# W-F-DX-C1_Display_PCB.net
KiCad netlist of a schematic drawn in Altium Designer
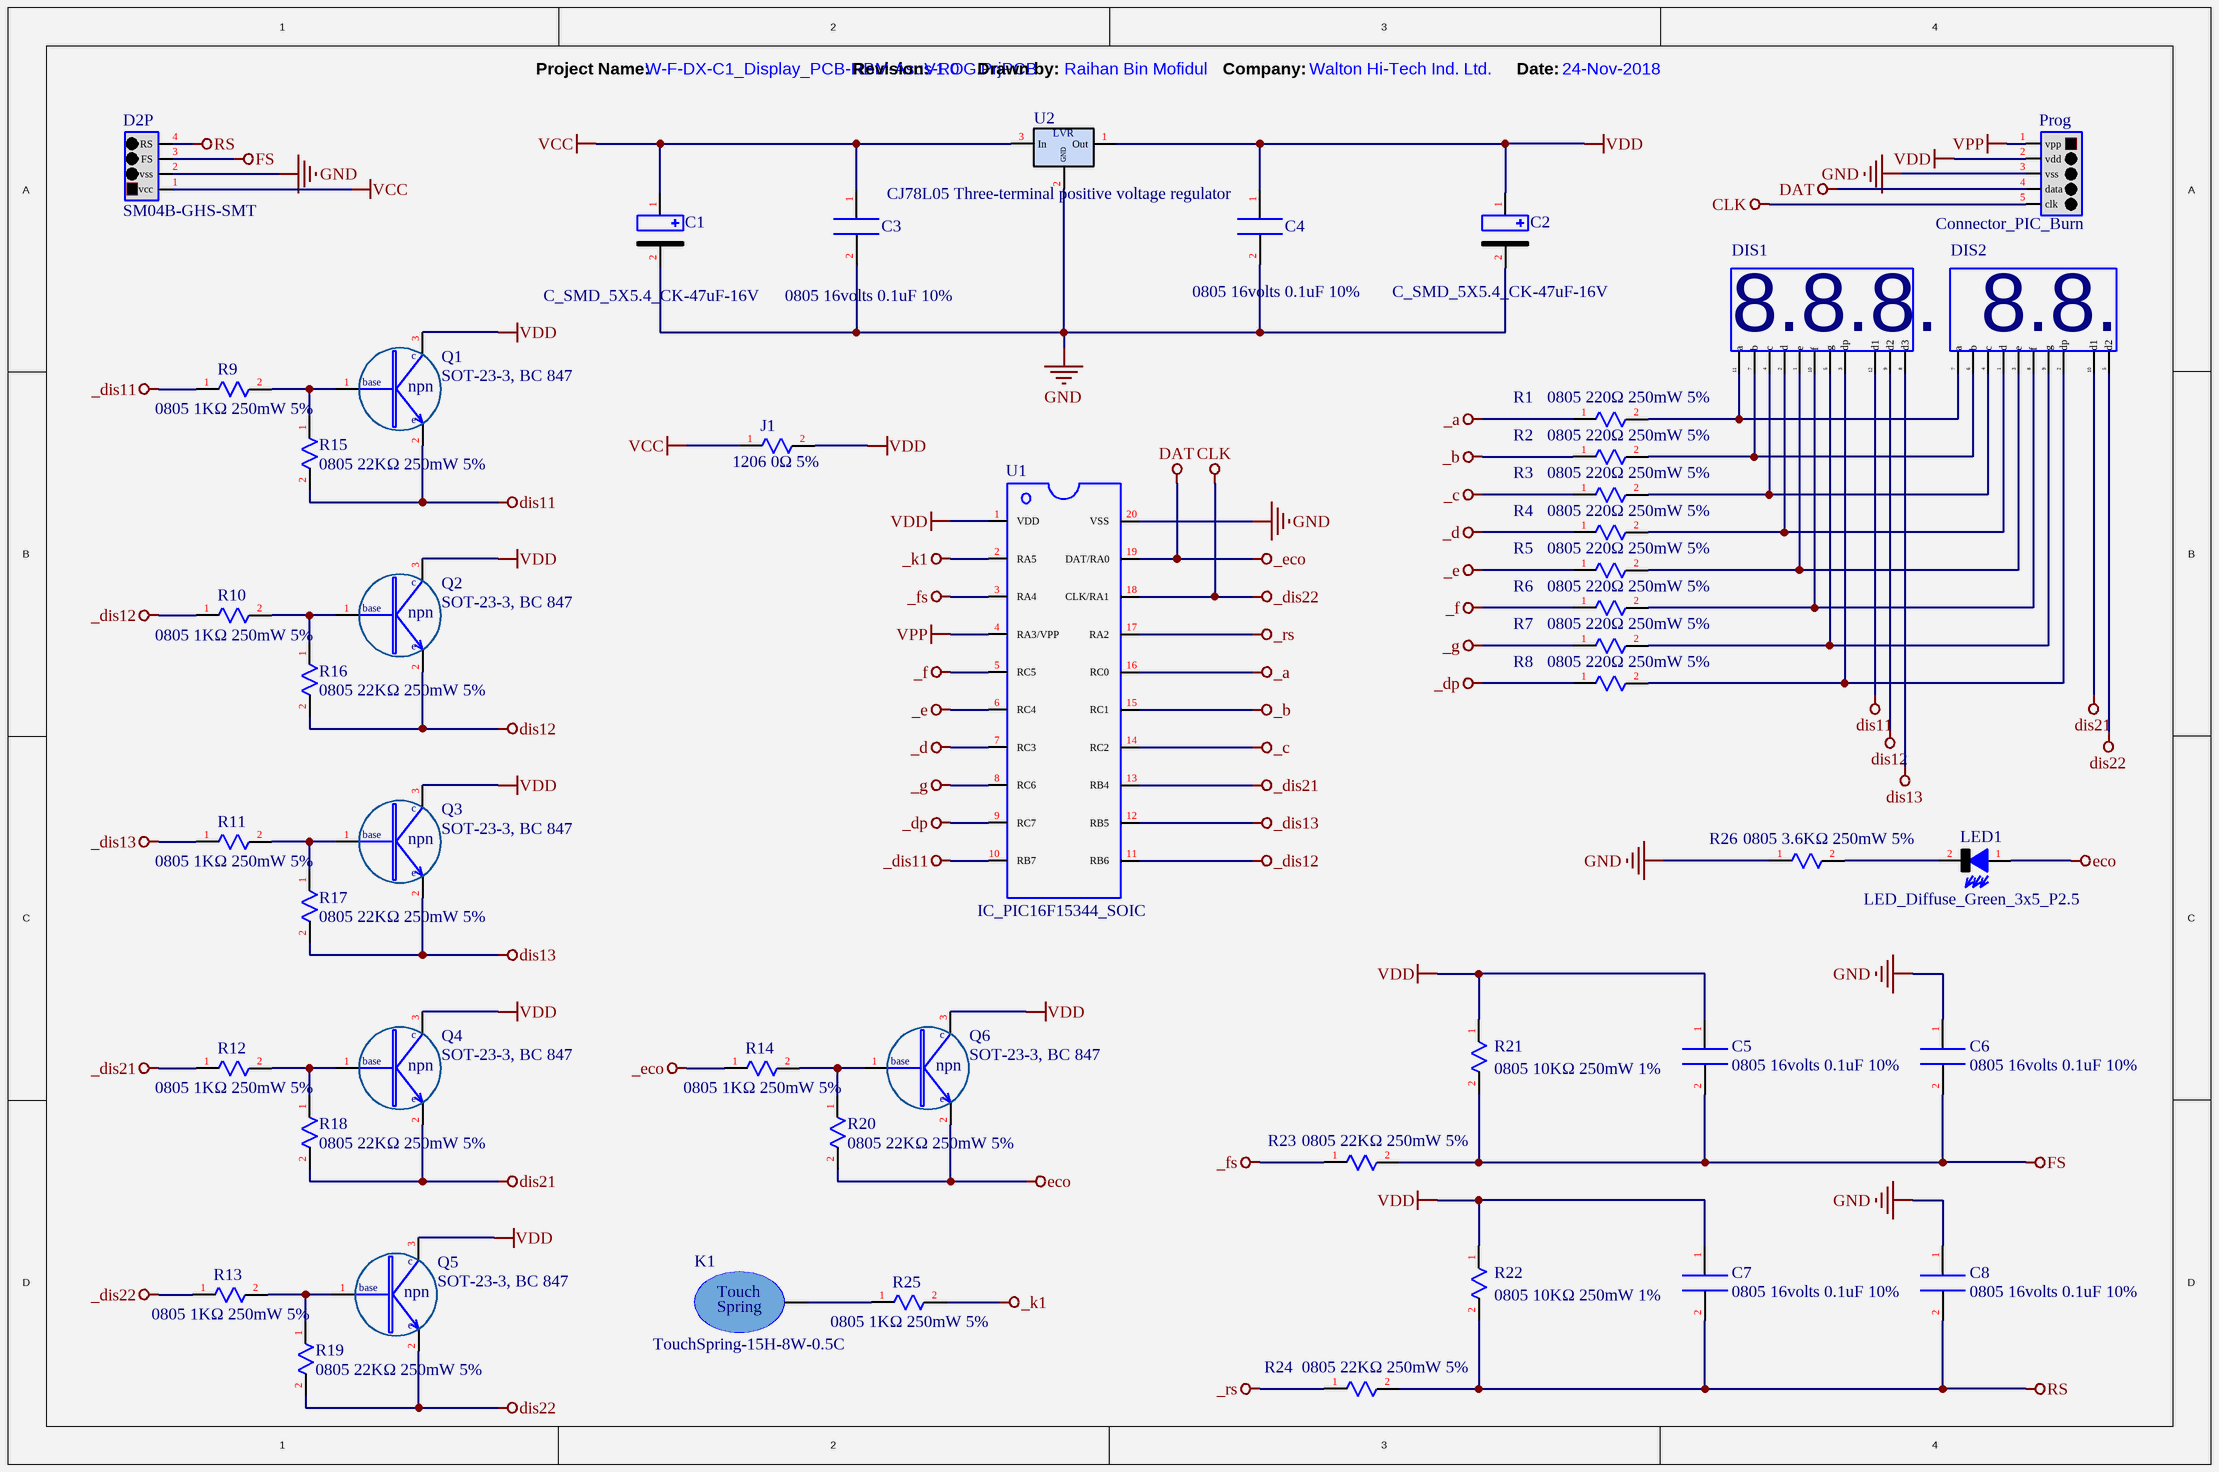
[diagram p0: W-F-DX-C1_Display_PCB.SchDoc]

(export (version "E")
  (design (tool "Eeschema 10.0.6"))
  (components
    (comp (ref "C1")
      (value "C_SMD_5X5.4_CK-47uF-16V")
      (footprint "C_SMD_5X5.4_CK-47uF-16V")
      (libsource (lib "RBM_SCH-Lib_17-Nov-18") (part "Capacitor Polar"))
    )
    (comp (ref "C2")
      (value "C_SMD_5X5.4_CK-47uF-16V")
      (footprint "C_SMD_5X5.4_CK-47uF-16V")
      (libsource (lib "RBM_SCH-Lib_17-Nov-18") (part "Capacitor Polar"))
    )
    (comp (ref "C3")
      (value "0805 16volts 0.1uF 10%")
      (footprint "C_0805")
      (libsource (lib "RBM_SCH-Lib_17-Nov-18") (part "Capacitor Non-Polar"))
    )
    (comp (ref "C4")
      (value "0805 16volts 0.1uF 10%")
      (footprint "C_0805")
      (libsource (lib "RBM_SCH-Lib_17-Nov-18") (part "Capacitor Non-Polar"))
    )
    (comp (ref "C5")
      (value "0805 16volts 0.1uF 10%")
      (footprint "C_0805")
      (libsource (lib "RBM_SCH-Lib_17-Nov-18") (part "Capacitor Non-Polar"))
    )
    (comp (ref "C6")
      (value "0805 16volts 0.1uF 10%")
      (footprint "C_0805")
      (libsource (lib "RBM_SCH-Lib_17-Nov-18") (part "Capacitor Non-Polar"))
    )
    (comp (ref "C7")
      (value "0805 16volts 0.1uF 10%")
      (footprint "C_0805")
      (libsource (lib "RBM_SCH-Lib_17-Nov-18") (part "Capacitor Non-Polar"))
    )
    (comp (ref "C8")
      (value "0805 16volts 0.1uF 10%")
      (footprint "C_0805")
      (libsource (lib "RBM_SCH-Lib_17-Nov-18") (part "Capacitor Non-Polar"))
    )
    (comp (ref "D2P")
      (value "SM04B-GHS-SMT")
      (footprint "CN_4P_A2001WR-S-XP-LCP")
      (libsource (lib "RBM_V1.0_Schlib") (part "Connector_4PINs"))
    )
    (comp (ref "DIS1")
      (value "Display_3Digits Seven Segment")
      (footprint "DIS_56\" 3 digit Display")
      (description "3 Digit Seven Segment Display CA")
      (libsource (lib "RBM_SCH-Lib_17-Nov-18") (part "Display_3Digits Seven Segment"))
    )
    (comp (ref "DIS2")
      (value "Display_2Digits Seven Segment")
      (footprint "Dis_56\" 2 digit Display")
      (description "2 Digit Seven Segment Display CA")
      (libsource (lib "RBM_SCH-Lib_17-Nov-18") (part "Display_2Digits Seven Segment"))
    )
    (comp (ref "J1")
      (value "1206 0Ω 5%")
      (footprint "R_1206")
      (libsource (lib "RBM_SCH-Lib_17-Nov-18") (part "Resistor"))
    )
    (comp (ref "K1")
      (value "TouchSpring-15H-8W-0.5C")
      (footprint "T_TouchSpring-15H-8W-0.5C")
      (libsource (lib "RBM_SCH-Lib_17-Nov-18") (part "Touch_Spring"))
    )
    (comp (ref "LED1")
      (value "LED_Diffuse_Green_3x5_P2.5")
      (footprint "LED_3x5_P2.5")
      (libsource (lib "RBM_SCH-Lib_17-Nov-18") (part "LED"))
    )
    (comp (ref "Prog")
      (value "Connector_PIC_Burn")
      (footprint "CN_PIC_MCU_Debugger")
      (libsource (lib "RBM_SCH-Lib_17-Nov-18") (part "Connector_PIC_Burn"))
    )
    (comp (ref "Q1")
      (value "SOT-23-3, BC 847")
      (footprint "Q_SOT-23-3_NPN_BC847")
      (libsource (lib "RBM_SCH-Lib_17-Nov-18") (part "BJT_npn"))
    )
    (comp (ref "Q2")
      (value "SOT-23-3, BC 847")
      (footprint "Q_SOT-23-3_NPN_BC847")
      (libsource (lib "RBM_SCH-Lib_17-Nov-18") (part "BJT_npn"))
    )
    (comp (ref "Q3")
      (value "SOT-23-3, BC 847")
      (footprint "Q_SOT-23-3_NPN_BC847")
      (libsource (lib "RBM_SCH-Lib_17-Nov-18") (part "BJT_npn"))
    )
    (comp (ref "Q4")
      (value "SOT-23-3, BC 847")
      (footprint "Q_SOT-23-3_NPN_BC847")
      (libsource (lib "RBM_SCH-Lib_17-Nov-18") (part "BJT_npn"))
    )
    (comp (ref "Q5")
      (value "SOT-23-3, BC 847")
      (footprint "Q_SOT-23-3_NPN_BC847")
      (libsource (lib "RBM_SCH-Lib_17-Nov-18") (part "BJT_npn"))
    )
    (comp (ref "Q6")
      (value "SOT-23-3, BC 847")
      (footprint "Q_SOT-23-3_NPN_BC847")
      (libsource (lib "RBM_SCH-Lib_17-Nov-18") (part "BJT_npn"))
    )
    (comp (ref "R1")
      (value "0805 220Ω 250mW 5%")
      (footprint "R_0805")
      (libsource (lib "RBM_SCH-Lib_17-Nov-18") (part "Resistor"))
    )
    (comp (ref "R2")
      (value "0805 220Ω 250mW 5%")
      (footprint "R_0805")
      (libsource (lib "RBM_SCH-Lib_17-Nov-18") (part "Resistor"))
    )
    (comp (ref "R3")
      (value "0805 220Ω 250mW 5%")
      (footprint "R_0805")
      (libsource (lib "RBM_SCH-Lib_17-Nov-18") (part "Resistor"))
    )
    (comp (ref "R4")
      (value "0805 220Ω 250mW 5%")
      (footprint "R_0805")
      (libsource (lib "RBM_SCH-Lib_17-Nov-18") (part "Resistor"))
    )
    (comp (ref "R5")
      (value "0805 220Ω 250mW 5%")
      (footprint "R_0805")
      (libsource (lib "RBM_SCH-Lib_17-Nov-18") (part "Resistor"))
    )
    (comp (ref "R6")
      (value "0805 220Ω 250mW 5%")
      (footprint "R_0805")
      (libsource (lib "RBM_SCH-Lib_17-Nov-18") (part "Resistor"))
    )
    (comp (ref "R7")
      (value "0805 220Ω 250mW 5%")
      (footprint "R_0805")
      (libsource (lib "RBM_SCH-Lib_17-Nov-18") (part "Resistor"))
    )
    (comp (ref "R8")
      (value "0805 220Ω 250mW 5%")
      (footprint "R_0805")
      (libsource (lib "RBM_SCH-Lib_17-Nov-18") (part "Resistor"))
    )
    (comp (ref "R9")
      (value "0805 1KΩ 250mW 5%")
      (footprint "R_0805")
      (libsource (lib "RBM_SCH-Lib_17-Nov-18") (part "Resistor"))
    )
    (comp (ref "R10")
      (value "0805 1KΩ 250mW 5%")
      (footprint "R_0805")
      (libsource (lib "RBM_SCH-Lib_17-Nov-18") (part "Resistor"))
    )
    (comp (ref "R11")
      (value "0805 1KΩ 250mW 5%")
      (footprint "R_0805")
      (libsource (lib "RBM_SCH-Lib_17-Nov-18") (part "Resistor"))
    )
    (comp (ref "R12")
      (value "0805 1KΩ 250mW 5%")
      (footprint "R_0805")
      (libsource (lib "RBM_SCH-Lib_17-Nov-18") (part "Resistor"))
    )
    (comp (ref "R13")
      (value "0805 1KΩ 250mW 5%")
      (footprint "R_0805")
      (libsource (lib "RBM_SCH-Lib_17-Nov-18") (part "Resistor"))
    )
    (comp (ref "R14")
      (value "0805 1KΩ 250mW 5%")
      (footprint "R_0805")
      (libsource (lib "RBM_SCH-Lib_17-Nov-18") (part "Resistor"))
    )
    (comp (ref "R15")
      (value "0805 22KΩ 250mW 5%")
      (footprint "R_0805")
      (libsource (lib "RBM_SCH-Lib_17-Nov-18") (part "Resistor"))
    )
    (comp (ref "R16")
      (value "0805 22KΩ 250mW 5%")
      (footprint "R_0805")
      (libsource (lib "RBM_SCH-Lib_17-Nov-18") (part "Resistor"))
    )
    (comp (ref "R17")
      (value "0805 22KΩ 250mW 5%")
      (footprint "R_0805")
      (libsource (lib "RBM_SCH-Lib_17-Nov-18") (part "Resistor"))
    )
    (comp (ref "R18")
      (value "0805 22KΩ 250mW 5%")
      (footprint "R_0805")
      (libsource (lib "RBM_SCH-Lib_17-Nov-18") (part "Resistor"))
    )
    (comp (ref "R19")
      (value "0805 22KΩ 250mW 5%")
      (footprint "R_0805")
      (libsource (lib "RBM_SCH-Lib_17-Nov-18") (part "Resistor"))
    )
    (comp (ref "R20")
      (value "0805 22KΩ 250mW 5%")
      (footprint "R_0805")
      (libsource (lib "RBM_SCH-Lib_17-Nov-18") (part "Resistor"))
    )
    (comp (ref "R21")
      (value "0805 10KΩ 250mW 1%")
      (footprint "R_0805")
      (libsource (lib "RBM_SCH-Lib_17-Nov-18") (part "Resistor"))
    )
    (comp (ref "R22")
      (value "0805 10KΩ 250mW 1%")
      (footprint "R_0805")
      (libsource (lib "RBM_SCH-Lib_17-Nov-18") (part "Resistor"))
    )
    (comp (ref "R23")
      (value "0805 22KΩ 250mW 5%")
      (footprint "R_0805")
      (libsource (lib "RBM_SCH-Lib_17-Nov-18") (part "Resistor"))
    )
    (comp (ref "R24")
      (value "0805 22KΩ 250mW 5%")
      (footprint "R_0805")
      (libsource (lib "RBM_SCH-Lib_17-Nov-18") (part "Resistor"))
    )
    (comp (ref "R25")
      (value "0805 1KΩ 250mW 5%")
      (footprint "R_0805")
      (libsource (lib "RBM_SCH-Lib_17-Nov-18") (part "Resistor"))
    )
    (comp (ref "R26")
      (value "0805 3.6KΩ 250mW 5%")
      (footprint "R_0805")
      (libsource (lib "RBM_SCH-Lib_17-Nov-18") (part "Resistor"))
    )
    (comp (ref "U1")
      (value "IC_PIC16F15344_SOIC")
      (footprint "U_PIC16F1XXXX_20pin_SOIC")
      (libsource (lib "RBM_SCH-Lib_17-Nov-18") (part "IC_PIC16F1XXXX_20PIN"))
    )
    (comp (ref "U2")
      (value "CJ78L05 Three-terminal positive voltage regulator")
      (footprint "U_CJ78L05_SOT89")
      (libsource (lib "RBM_SCH-Lib_17-Nov-18") (part "Voltage Regulator_CJ78L05"))
    )
  )
  (nets
    (net (code "1") (name "CLK") (class "Default")
      (node (ref "Prog") (pin "5") (pinfunction "clk_5") (pintype "passive"))
      (node (ref "R13") (pin "1") (pinfunction "1_1") (pintype "passive"))
      (node (ref "U1") (pin "18") (pinfunction "CLK/RA1_18") (pintype "passive"))
    )
    (net (code "2") (name "DAT") (class "Default")
      (node (ref "Prog") (pin "4") (pinfunction "data_4") (pintype "passive"))
      (node (ref "R14") (pin "1") (pinfunction "1_1") (pintype "passive"))
      (node (ref "U1") (pin "19") (pinfunction "DAT/RA0_19") (pintype "passive"))
    )
    (net (code "3") (name "FS") (class "Default")
      (node (ref "C5") (pin "2") (pinfunction "2_2") (pintype "passive"))
      (node (ref "C6") (pin "2") (pinfunction "2_2") (pintype "passive"))
      (node (ref "D2P") (pin "3") (pinfunction "FS_3") (pintype "passive"))
      (node (ref "R21") (pin "2") (pinfunction "2_2") (pintype "passive"))
      (node (ref "R23") (pin "2") (pinfunction "2_2") (pintype "passive"))
    )
    (net (code "4") (name "GND") (class "Default")
      (node (ref "C1") (pin "2") (pinfunction "vss_2") (pintype "passive"))
      (node (ref "C2") (pin "2") (pinfunction "vss_2") (pintype "passive"))
      (node (ref "C3") (pin "2") (pinfunction "2_2") (pintype "passive"))
      (node (ref "C4") (pin "2") (pinfunction "2_2") (pintype "passive"))
      (node (ref "C6") (pin "1") (pinfunction "1_1") (pintype "passive"))
      (node (ref "C8") (pin "1") (pinfunction "1_1") (pintype "passive"))
      (node (ref "D2P") (pin "2") (pinfunction "vss_2") (pintype "passive"))
      (node (ref "Prog") (pin "3") (pinfunction "vss_3") (pintype "passive"))
      (node (ref "R26") (pin "1") (pinfunction "1_1") (pintype "passive"))
      (node (ref "U1") (pin "20") (pinfunction "VSS_20") (pintype "passive"))
      (node (ref "U2") (pin "2") (pinfunction "GND_2") (pintype "passive"))
    )
    (net (code "5") (name "Net-(DIS1-a)") (class "Default")
      (node (ref "DIS1") (pin "11") (pinfunction "a_11") (pintype "passive"))
      (node (ref "DIS2") (pin "7") (pinfunction "a_7") (pintype "passive"))
      (node (ref "R1") (pin "2") (pinfunction "2_2") (pintype "passive"))
    )
    (net (code "6") (name "Net-(DIS1-b)") (class "Default")
      (node (ref "DIS1") (pin "7") (pinfunction "b_7") (pintype "passive"))
      (node (ref "DIS2") (pin "6") (pinfunction "b_6") (pintype "passive"))
      (node (ref "R2") (pin "2") (pinfunction "2_2") (pintype "passive"))
    )
    (net (code "7") (name "Net-(DIS1-c)") (class "Default")
      (node (ref "DIS1") (pin "4") (pinfunction "c_4") (pintype "passive"))
      (node (ref "DIS2") (pin "4") (pinfunction "c_4") (pintype "passive"))
      (node (ref "R3") (pin "2") (pinfunction "2_2") (pintype "passive"))
    )
    (net (code "8") (name "Net-(DIS1-d)") (class "Default")
      (node (ref "DIS1") (pin "2") (pinfunction "d_2") (pintype "passive"))
      (node (ref "DIS2") (pin "1") (pinfunction "d_1") (pintype "passive"))
      (node (ref "R4") (pin "2") (pinfunction "2_2") (pintype "passive"))
    )
    (net (code "9") (name "Net-(DIS1-dp)") (class "Default")
      (node (ref "DIS1") (pin "3") (pinfunction "dp_3") (pintype "passive"))
      (node (ref "DIS2") (pin "2") (pinfunction "dp_2") (pintype "passive"))
      (node (ref "R8") (pin "2") (pinfunction "2_2") (pintype "passive"))
    )
    (net (code "10") (name "Net-(DIS1-e)") (class "Default")
      (node (ref "DIS1") (pin "1") (pinfunction "e_1") (pintype "passive"))
      (node (ref "DIS2") (pin "3") (pinfunction "e_3") (pintype "passive"))
      (node (ref "R5") (pin "2") (pinfunction "2_2") (pintype "passive"))
    )
    (net (code "11") (name "Net-(DIS1-f)") (class "Default")
      (node (ref "DIS1") (pin "10") (pinfunction "f_10") (pintype "passive"))
      (node (ref "DIS2") (pin "8") (pinfunction "f_8") (pintype "passive"))
      (node (ref "R6") (pin "2") (pinfunction "2_2") (pintype "passive"))
    )
    (net (code "12") (name "Net-(DIS1-g)") (class "Default")
      (node (ref "DIS1") (pin "5") (pinfunction "g_5") (pintype "passive"))
      (node (ref "DIS2") (pin "9") (pinfunction "g_9") (pintype "passive"))
      (node (ref "R7") (pin "2") (pinfunction "2_2") (pintype "passive"))
    )
    (net (code "13") (name "Net-(K1-Pad1)") (class "Default")
      (node (ref "K1") (pin "1") (pinfunction "1_1") (pintype "passive"))
      (node (ref "R25") (pin "1") (pinfunction "1_1") (pintype "passive"))
    )
    (net (code "14") (name "Net-(LED1-vss)") (class "Default")
      (node (ref "LED1") (pin "2") (pinfunction "vss_2") (pintype "passive"))
      (node (ref "R26") (pin "2") (pinfunction "2_2") (pintype "passive"))
    )
    (net (code "15") (name "Net-(Q1-Base)") (class "Default")
      (node (ref "Q1") (pin "1") (pinfunction "Base_1") (pintype "passive"))
      (node (ref "R15") (pin "1") (pinfunction "1_1") (pintype "passive"))
      (node (ref "R9") (pin "2") (pinfunction "2_2") (pintype "passive"))
    )
    (net (code "16") (name "Net-(Q2-Base)") (class "Default")
      (node (ref "Q2") (pin "1") (pinfunction "Base_1") (pintype "passive"))
      (node (ref "R10") (pin "2") (pinfunction "2_2") (pintype "passive"))
      (node (ref "R16") (pin "1") (pinfunction "1_1") (pintype "passive"))
    )
    (net (code "17") (name "Net-(Q3-Base)") (class "Default")
      (node (ref "Q3") (pin "1") (pinfunction "Base_1") (pintype "passive"))
      (node (ref "R11") (pin "2") (pinfunction "2_2") (pintype "passive"))
      (node (ref "R17") (pin "1") (pinfunction "1_1") (pintype "passive"))
    )
    (net (code "18") (name "Net-(Q4-Base)") (class "Default")
      (node (ref "Q4") (pin "1") (pinfunction "Base_1") (pintype "passive"))
      (node (ref "R12") (pin "2") (pinfunction "2_2") (pintype "passive"))
      (node (ref "R18") (pin "1") (pinfunction "1_1") (pintype "passive"))
    )
    (net (code "19") (name "Net-(Q5-Base)") (class "Default")
      (node (ref "Q5") (pin "1") (pinfunction "Base_1") (pintype "passive"))
      (node (ref "R13") (pin "2") (pinfunction "2_2") (pintype "passive"))
      (node (ref "R19") (pin "1") (pinfunction "1_1") (pintype "passive"))
    )
    (net (code "20") (name "Net-(Q6-Base)") (class "Default")
      (node (ref "Q6") (pin "1") (pinfunction "Base_1") (pintype "passive"))
      (node (ref "R14") (pin "2") (pinfunction "2_2") (pintype "passive"))
      (node (ref "R20") (pin "1") (pinfunction "1_1") (pintype "passive"))
    )
    (net (code "21") (name "RS") (class "Default")
      (node (ref "C7") (pin "2") (pinfunction "2_2") (pintype "passive"))
      (node (ref "C8") (pin "2") (pinfunction "2_2") (pintype "passive"))
      (node (ref "D2P") (pin "4") (pinfunction "RS_4") (pintype "passive"))
      (node (ref "R22") (pin "2") (pinfunction "2_2") (pintype "passive"))
      (node (ref "R24") (pin "2") (pinfunction "2_2") (pintype "passive"))
    )
    (net (code "22") (name "VCC") (class "Default")
      (node (ref "C1") (pin "1") (pinfunction "vdd_1") (pintype "passive"))
      (node (ref "C3") (pin "1") (pinfunction "1_1") (pintype "passive"))
      (node (ref "D2P") (pin "1") (pinfunction "vcc_1") (pintype "passive"))
      (node (ref "J1") (pin "1") (pinfunction "1_1") (pintype "passive"))
      (node (ref "U2") (pin "3") (pinfunction "In_3") (pintype "passive"))
    )
    (net (code "23") (name "VDD") (class "Default")
      (node (ref "C2") (pin "1") (pinfunction "vdd_1") (pintype "passive"))
      (node (ref "C4") (pin "1") (pinfunction "1_1") (pintype "passive"))
      (node (ref "C5") (pin "1") (pinfunction "1_1") (pintype "passive"))
      (node (ref "C7") (pin "1") (pinfunction "1_1") (pintype "passive"))
      (node (ref "J1") (pin "2") (pinfunction "2_2") (pintype "passive"))
      (node (ref "Prog") (pin "2") (pinfunction "vdd_2") (pintype "passive"))
      (node (ref "Q1") (pin "3") (pinfunction "Collector_3") (pintype "passive"))
      (node (ref "Q2") (pin "3") (pinfunction "Collector_3") (pintype "passive"))
      (node (ref "Q3") (pin "3") (pinfunction "Collector_3") (pintype "passive"))
      (node (ref "Q4") (pin "3") (pinfunction "Collector_3") (pintype "passive"))
      (node (ref "Q5") (pin "3") (pinfunction "Collector_3") (pintype "passive"))
      (node (ref "Q6") (pin "3") (pinfunction "Collector_3") (pintype "passive"))
      (node (ref "R21") (pin "1") (pinfunction "1_1") (pintype "passive"))
      (node (ref "R22") (pin "1") (pinfunction "1_1") (pintype "passive"))
      (node (ref "U1") (pin "1") (pinfunction "VDD_1") (pintype "passive"))
      (node (ref "U2") (pin "1") (pinfunction "Out_1") (pintype "passive"))
    )
    (net (code "24") (name "VPP") (class "Default")
      (node (ref "Prog") (pin "1") (pinfunction "vpp_1") (pintype "passive"))
      (node (ref "U1") (pin "4") (pinfunction "RA3/VPP_4") (pintype "passive"))
    )
    (net (code "25") (name "_a") (class "Default")
      (node (ref "R1") (pin "1") (pinfunction "1_1") (pintype "passive"))
      (node (ref "U1") (pin "16") (pinfunction "RC0_16") (pintype "passive"))
    )
    (net (code "26") (name "_b") (class "Default")
      (node (ref "R2") (pin "1") (pinfunction "1_1") (pintype "passive"))
      (node (ref "U1") (pin "15") (pinfunction "RC1_15") (pintype "passive"))
    )
    (net (code "27") (name "_c") (class "Default")
      (node (ref "R3") (pin "1") (pinfunction "1_1") (pintype "passive"))
      (node (ref "U1") (pin "14") (pinfunction "RC2_14") (pintype "passive"))
    )
    (net (code "28") (name "_d") (class "Default")
      (node (ref "R4") (pin "1") (pinfunction "1_1") (pintype "passive"))
      (node (ref "U1") (pin "7") (pinfunction "RC3_7") (pintype "passive"))
    )
    (net (code "29") (name "_dis11") (class "Default")
      (node (ref "R9") (pin "1") (pinfunction "1_1") (pintype "passive"))
      (node (ref "U1") (pin "10") (pinfunction "RB7_10") (pintype "passive"))
    )
    (net (code "30") (name "_dis12") (class "Default")
      (node (ref "R10") (pin "1") (pinfunction "1_1") (pintype "passive"))
      (node (ref "U1") (pin "11") (pinfunction "RB6_11") (pintype "passive"))
    )
    (net (code "31") (name "_dis13") (class "Default")
      (node (ref "R11") (pin "1") (pinfunction "1_1") (pintype "passive"))
      (node (ref "U1") (pin "12") (pinfunction "RB5_12") (pintype "passive"))
    )
    (net (code "32") (name "_dis21") (class "Default")
      (node (ref "R12") (pin "1") (pinfunction "1_1") (pintype "passive"))
      (node (ref "U1") (pin "13") (pinfunction "RB4_13") (pintype "passive"))
    )
    (net (code "33") (name "_dp") (class "Default")
      (node (ref "R8") (pin "1") (pinfunction "1_1") (pintype "passive"))
      (node (ref "U1") (pin "9") (pinfunction "RC7_9") (pintype "passive"))
    )
    (net (code "34") (name "_e") (class "Default")
      (node (ref "R5") (pin "1") (pinfunction "1_1") (pintype "passive"))
      (node (ref "U1") (pin "6") (pinfunction "RC4_6") (pintype "passive"))
    )
    (net (code "35") (name "_f") (class "Default")
      (node (ref "R6") (pin "1") (pinfunction "1_1") (pintype "passive"))
      (node (ref "U1") (pin "5") (pinfunction "RC5_5") (pintype "passive"))
    )
    (net (code "36") (name "_fs") (class "Default")
      (node (ref "R23") (pin "1") (pinfunction "1_1") (pintype "passive"))
      (node (ref "U1") (pin "3") (pinfunction "RA4_3") (pintype "passive"))
    )
    (net (code "37") (name "_g") (class "Default")
      (node (ref "R7") (pin "1") (pinfunction "1_1") (pintype "passive"))
      (node (ref "U1") (pin "8") (pinfunction "RC6_8") (pintype "passive"))
    )
    (net (code "38") (name "_k1") (class "Default")
      (node (ref "R25") (pin "2") (pinfunction "2_2") (pintype "passive"))
      (node (ref "U1") (pin "2") (pinfunction "RA5_2") (pintype "passive"))
    )
    (net (code "39") (name "_rs") (class "Default")
      (node (ref "R24") (pin "1") (pinfunction "1_1") (pintype "passive"))
      (node (ref "U1") (pin "17") (pinfunction "RA2_17") (pintype "passive"))
    )
    (net (code "40") (name "dis11") (class "Default")
      (node (ref "DIS1") (pin "12") (pinfunction "d1_12") (pintype "passive"))
      (node (ref "Q1") (pin "2") (pinfunction "Emitter_2") (pintype "passive"))
      (node (ref "R15") (pin "2") (pinfunction "2_2") (pintype "passive"))
    )
    (net (code "41") (name "dis12") (class "Default")
      (node (ref "DIS1") (pin "9") (pinfunction "d2_9") (pintype "passive"))
      (node (ref "Q2") (pin "2") (pinfunction "Emitter_2") (pintype "passive"))
      (node (ref "R16") (pin "2") (pinfunction "2_2") (pintype "passive"))
    )
    (net (code "42") (name "dis13") (class "Default")
      (node (ref "DIS1") (pin "8") (pinfunction "d3_8") (pintype "passive"))
      (node (ref "Q3") (pin "2") (pinfunction "Emitter_2") (pintype "passive"))
      (node (ref "R17") (pin "2") (pinfunction "2_2") (pintype "passive"))
    )
    (net (code "43") (name "dis21") (class "Default")
      (node (ref "DIS2") (pin "10") (pinfunction "d1_10") (pintype "passive"))
      (node (ref "Q4") (pin "2") (pinfunction "Emitter_2") (pintype "passive"))
      (node (ref "R18") (pin "2") (pinfunction "2_2") (pintype "passive"))
    )
    (net (code "44") (name "dis22") (class "Default")
      (node (ref "DIS2") (pin "5") (pinfunction "d2_5") (pintype "passive"))
      (node (ref "Q5") (pin "2") (pinfunction "Emitter_2") (pintype "passive"))
      (node (ref "R19") (pin "2") (pinfunction "2_2") (pintype "passive"))
    )
    (net (code "45") (name "eco") (class "Default")
      (node (ref "LED1") (pin "1") (pinfunction "vdd_1") (pintype "passive"))
      (node (ref "Q6") (pin "2") (pinfunction "Emitter_2") (pintype "passive"))
      (node (ref "R20") (pin "2") (pinfunction "2_2") (pintype "passive"))
    )
  )
)
